# EskonzoUSB_base.net
KiCad netlist of a schematic drawn in EAGLE
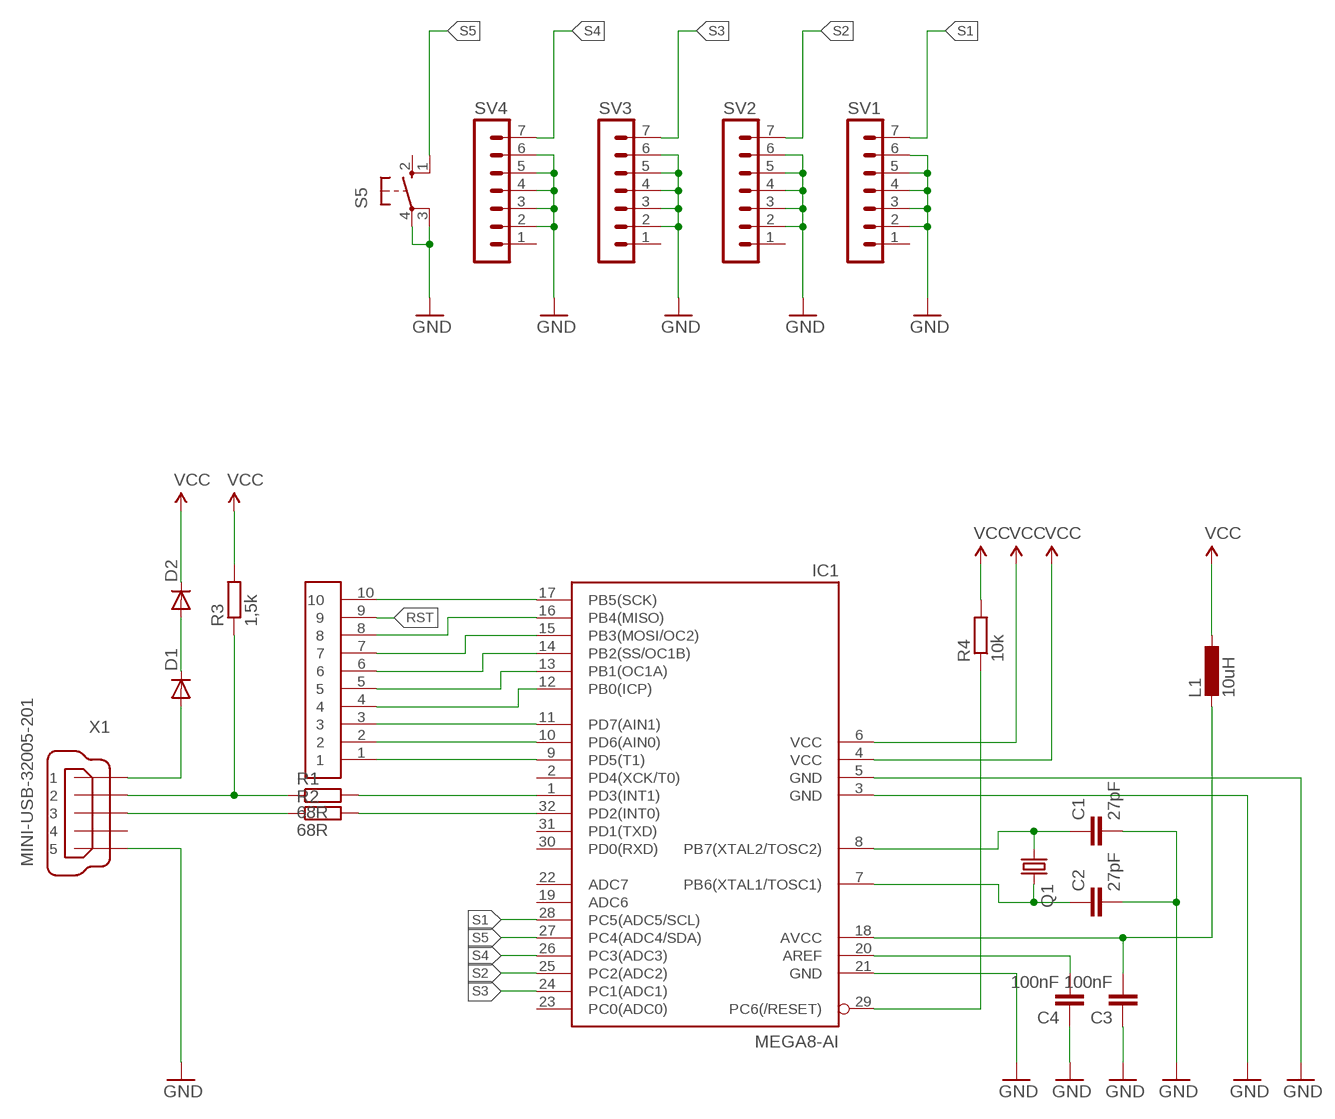
[diagram p0: schematic, sheet 1]

(export (version "E")
  (design (tool "Eeschema 10.0.6"))
  (components
    (comp (ref "C1")
      (value "27pF")
      (footprint "eagle-import:C0805")
      (libsource (lib "eagle-import") (part "C-EUC0805"))
    )
    (comp (ref "C2")
      (value "27pF")
      (footprint "eagle-import:C0805")
      (libsource (lib "eagle-import") (part "C-EUC0805"))
    )
    (comp (ref "C3")
      (value "100nF")
      (footprint "eagle-import:C0805")
      (libsource (lib "eagle-import") (part "C-EUC0805"))
    )
    (comp (ref "C4")
      (value "100nF")
      (footprint "eagle-import:C0805")
      (libsource (lib "eagle-import") (part "C-EUC0805"))
    )
    (comp (ref "D1")
      (value "DIODE-MELF-MLL41")
      (footprint "eagle-import:MELF-MLL41")
      (libsource (lib "eagle-import") (part "DIODE-MELF-MLL41"))
    )
    (comp (ref "D2")
      (value "DIODE-MELF-MLL41")
      (footprint "eagle-import:MELF-MLL41")
      (libsource (lib "eagle-import") (part "DIODE-MELF-MLL41"))
    )
    (comp (ref "IC1")
      (value "MEGA8-AI")
      (footprint "eagle-import:TQFP32-08")
      (fields (field (name "MPN") "ATMEGA8-16AU"))
      (libsource (lib "eagle-import") (part "MEGA8-AI"))
    )
    (comp (ref "L1")
      (value "10uH")
      (footprint "eagle-import:L1812")
      (libsource (lib "eagle-import") (part "L-EUL1812"))
    )
    (comp (ref "Q1")
      (value "CRYSTALHC49UP")
      (footprint "eagle-import:HC49UP")
      (libsource (lib "eagle-import") (part "CRYSTALHC49UP"))
    )
    (comp (ref "R1")
      (value "68R")
      (footprint "eagle-import:R0805")
      (libsource (lib "eagle-import") (part "R-EU_R0805"))
    )
    (comp (ref "R2")
      (value "68R")
      (footprint "eagle-import:R0805")
      (libsource (lib "eagle-import") (part "R-EU_R0805"))
    )
    (comp (ref "R3")
      (value "1,5k")
      (footprint "eagle-import:R0805")
      (libsource (lib "eagle-import") (part "R-EU_R0805"))
    )
    (comp (ref "R4")
      (value "10k")
      (footprint "eagle-import:R0805")
      (libsource (lib "eagle-import") (part "R-EU_R0805"))
    )
    (comp (ref "S5")
      (value "40-XX_SMD")
      (footprint "eagle-import:B3F-40XX_SMD")
      (libsource (lib "eagle-import") (part "40-XX_SMD"))
    )
    (comp (ref "SV1")
      (value "MA07-1_SMD")
      (footprint "eagle-import:MA07-1_SMD")
      (libsource (lib "eagle-import") (part "MA07-1_SMD"))
    )
    (comp (ref "SV2")
      (value "MA07-1_SMD")
      (footprint "eagle-import:MA07-1_SMD")
      (libsource (lib "eagle-import") (part "MA07-1_SMD"))
    )
    (comp (ref "SV3")
      (value "MA07-1_SMD")
      (footprint "eagle-import:MA07-1_SMD")
      (libsource (lib "eagle-import") (part "MA07-1_SMD"))
    )
    (comp (ref "SV4")
      (value "MA07-1_SMD")
      (footprint "eagle-import:MA07-1_SMD")
      (libsource (lib "eagle-import") (part "MA07-1_SMD"))
    )
    (comp (ref "U$1")
      (value "PINY_1X9_1.27MM_SMT")
      (footprint "eagle-import:PINY_1X9_1.27MM_SMT")
      (libsource (lib "eagle-import") (part "PINY_1X9_1.27MM_SMT"))
    )
    (comp (ref "X1")
      (value "MINI-USB-32005-201")
      (footprint "eagle-import:32005-201")
      (libsource (lib "eagle-import") (part "MINI-USB-32005-201"))
    )
  )
  (nets
    (net (code "1") (name "GND") (class "Default")
      (node (ref "C1") (pin "2") (pinfunction "2_2") (pintype "passive"))
      (node (ref "C2") (pin "2") (pinfunction "2_2") (pintype "passive"))
      (node (ref "C3") (pin "1") (pinfunction "1_1") (pintype "passive"))
      (node (ref "C4") (pin "1") (pinfunction "1_1") (pintype "passive"))
      (node (ref "IC1") (pin "21") (pinfunction "GND_21") (pintype "power_in"))
      (node (ref "IC1") (pin "3") (pinfunction "GND_3") (pintype "power_in"))
      (node (ref "IC1") (pin "5") (pinfunction "GND_5") (pintype "power_in"))
      (node (ref "S5") (pin "3") (pinfunction "P1_3") (pintype "passive"))
      (node (ref "S5") (pin "4") (pinfunction "P_4") (pintype "passive"))
      (node (ref "SV1") (pin "2") (pinfunction "2_2") (pintype "passive"))
      (node (ref "SV1") (pin "3") (pinfunction "3_3") (pintype "passive"))
      (node (ref "SV1") (pin "4") (pinfunction "4_4") (pintype "passive"))
      (node (ref "SV1") (pin "5") (pinfunction "5_5") (pintype "passive"))
      (node (ref "SV1") (pin "6") (pinfunction "6_6") (pintype "passive"))
      (node (ref "SV2") (pin "2") (pinfunction "2_2") (pintype "passive"))
      (node (ref "SV2") (pin "3") (pinfunction "3_3") (pintype "passive"))
      (node (ref "SV2") (pin "4") (pinfunction "4_4") (pintype "passive"))
      (node (ref "SV2") (pin "5") (pinfunction "5_5") (pintype "passive"))
      (node (ref "SV2") (pin "6") (pinfunction "6_6") (pintype "passive"))
      (node (ref "SV3") (pin "2") (pinfunction "2_2") (pintype "passive"))
      (node (ref "SV3") (pin "3") (pinfunction "3_3") (pintype "passive"))
      (node (ref "SV3") (pin "4") (pinfunction "4_4") (pintype "passive"))
      (node (ref "SV3") (pin "5") (pinfunction "5_5") (pintype "passive"))
      (node (ref "SV3") (pin "6") (pinfunction "6_6") (pintype "passive"))
      (node (ref "SV4") (pin "2") (pinfunction "2_2") (pintype "passive"))
      (node (ref "SV4") (pin "3") (pinfunction "3_3") (pintype "passive"))
      (node (ref "SV4") (pin "4") (pinfunction "4_4") (pintype "passive"))
      (node (ref "SV4") (pin "5") (pinfunction "5_5") (pintype "passive"))
      (node (ref "SV4") (pin "6") (pinfunction "6_6") (pintype "passive"))
      (node (ref "X1") (pin "5") (pinfunction "5_5") (pintype "passive"))
    )
    (net (code "2") (name "Net-(D1-PadA)") (class "Default")
      (node (ref "D1") (pin "A") (pinfunction "A_A") (pintype "passive"))
      (node (ref "X1") (pin "1") (pinfunction "1_1") (pintype "passive"))
    )
    (net (code "3") (name "Net-(D1-PadC)") (class "Default")
      (node (ref "D1") (pin "C") (pinfunction "C_C") (pintype "passive"))
      (node (ref "D2") (pin "A") (pinfunction "A_A") (pintype "passive"))
    )
    (net (code "4") (name "Net-(IC1-AREF)") (class "Default")
      (node (ref "C4") (pin "2") (pinfunction "2_2") (pintype "passive"))
      (node (ref "IC1") (pin "20") (pinfunction "AREF_20") (pintype "passive"))
    )
    (net (code "5") (name "Net-(IC1-AVCC)") (class "Default")
      (node (ref "C3") (pin "2") (pinfunction "2_2") (pintype "passive"))
      (node (ref "IC1") (pin "18") (pinfunction "AVCC_18") (pintype "power_in"))
      (node (ref "L1") (pin "2") (pinfunction "2_2") (pintype "passive"))
    )
    (net (code "6") (name "Net-(IC1-PB0(ICP))") (class "Default")
      (node (ref "IC1") (pin "12") (pinfunction "PB0(ICP)_12") (pintype "bidirectional"))
      (node (ref "U$1") (pin "4") (pinfunction "4_4") (pintype "passive"))
    )
    (net (code "7") (name "Net-(IC1-PB1(OC1A))") (class "Default")
      (node (ref "IC1") (pin "13") (pinfunction "PB1(OC1A)_13") (pintype "bidirectional"))
      (node (ref "U$1") (pin "5") (pinfunction "5_5") (pintype "passive"))
    )
    (net (code "8") (name "Net-(IC1-PB2(SS{slash}OC1B))") (class "Default")
      (node (ref "IC1") (pin "14") (pinfunction "PB2(SS/OC1B)_14") (pintype "bidirectional"))
      (node (ref "U$1") (pin "6") (pinfunction "6_6") (pintype "passive"))
    )
    (net (code "9") (name "Net-(IC1-PB3(MOSI{slash}OC2))") (class "Default")
      (node (ref "IC1") (pin "15") (pinfunction "PB3(MOSI/OC2)_15") (pintype "bidirectional"))
      (node (ref "U$1") (pin "7") (pinfunction "7_7") (pintype "passive"))
    )
    (net (code "10") (name "Net-(IC1-PB4(MISO))") (class "Default")
      (node (ref "IC1") (pin "16") (pinfunction "PB4(MISO)_16") (pintype "bidirectional"))
      (node (ref "U$1") (pin "8") (pinfunction "8_8") (pintype "passive"))
    )
    (net (code "11") (name "Net-(IC1-PB5(SCK))") (class "Default")
      (node (ref "IC1") (pin "17") (pinfunction "PB5(SCK)_17") (pintype "bidirectional"))
      (node (ref "U$1") (pin "10") (pinfunction "10_10") (pintype "passive"))
    )
    (net (code "12") (name "Net-(IC1-PB6(XTAL1{slash}TOSC1))") (class "Default")
      (node (ref "C2") (pin "1") (pinfunction "1_1") (pintype "passive"))
      (node (ref "IC1") (pin "7") (pinfunction "PB6(XTAL1/TOSC1)_7") (pintype "bidirectional"))
      (node (ref "Q1") (pin "2") (pinfunction "2_2") (pintype "passive"))
    )
    (net (code "13") (name "Net-(IC1-PB7(XTAL2{slash}TOSC2))") (class "Default")
      (node (ref "C1") (pin "1") (pinfunction "1_1") (pintype "passive"))
      (node (ref "IC1") (pin "8") (pinfunction "PB7(XTAL2/TOSC2)_8") (pintype "bidirectional"))
      (node (ref "Q1") (pin "1") (pinfunction "1_1") (pintype "passive"))
    )
    (net (code "14") (name "Net-(IC1-PD2(INT0))") (class "Default")
      (node (ref "IC1") (pin "32") (pinfunction "PD2(INT0)_32") (pintype "bidirectional"))
      (node (ref "R2") (pin "2") (pinfunction "2_2") (pintype "passive"))
    )
    (net (code "15") (name "Net-(IC1-PD3(INT1))") (class "Default")
      (node (ref "IC1") (pin "1") (pinfunction "PD3(INT1)_1") (pintype "bidirectional"))
      (node (ref "R1") (pin "2") (pinfunction "2_2") (pintype "passive"))
    )
    (net (code "16") (name "Net-(IC1-PD5(T1))") (class "Default")
      (node (ref "IC1") (pin "9") (pinfunction "PD5(T1)_9") (pintype "bidirectional"))
      (node (ref "U$1") (pin "1") (pinfunction "1_1") (pintype "passive"))
    )
    (net (code "17") (name "Net-(IC1-PD6(AIN0))") (class "Default")
      (node (ref "IC1") (pin "10") (pinfunction "PD6(AIN0)_10") (pintype "bidirectional"))
      (node (ref "U$1") (pin "2") (pinfunction "2_2") (pintype "passive"))
    )
    (net (code "18") (name "Net-(IC1-PD7(AIN1))") (class "Default")
      (node (ref "IC1") (pin "11") (pinfunction "PD7(AIN1)_11") (pintype "bidirectional"))
      (node (ref "U$1") (pin "3") (pinfunction "3_3") (pintype "passive"))
    )
    (net (code "19") (name "Net-(R1-Pad1)") (class "Default")
      (node (ref "R1") (pin "1") (pinfunction "1_1") (pintype "passive"))
      (node (ref "R3") (pin "1") (pinfunction "1_1") (pintype "passive"))
      (node (ref "X1") (pin "2") (pinfunction "2_2") (pintype "passive"))
    )
    (net (code "20") (name "Net-(R2-Pad1)") (class "Default")
      (node (ref "R2") (pin "1") (pinfunction "1_1") (pintype "passive"))
      (node (ref "X1") (pin "3") (pinfunction "3_3") (pintype "passive"))
    )
    (net (code "21") (name "RST") (class "Default")
      (node (ref "IC1") (pin "29") (pinfunction "PC6(/RESET)_29") (pintype "bidirectional"))
      (node (ref "R4") (pin "1") (pinfunction "1_1") (pintype "passive"))
      (node (ref "U$1") (pin "9") (pinfunction "9_9") (pintype "passive"))
    )
    (net (code "22") (name "S1") (class "Default")
      (node (ref "IC1") (pin "28") (pinfunction "PC5(ADC5/SCL)_28") (pintype "bidirectional"))
      (node (ref "SV1") (pin "7") (pinfunction "7_7") (pintype "passive"))
    )
    (net (code "23") (name "S2") (class "Default")
      (node (ref "IC1") (pin "25") (pinfunction "PC2(ADC2)_25") (pintype "bidirectional"))
      (node (ref "SV2") (pin "7") (pinfunction "7_7") (pintype "passive"))
    )
    (net (code "24") (name "S3") (class "Default")
      (node (ref "IC1") (pin "24") (pinfunction "PC1(ADC1)_24") (pintype "bidirectional"))
      (node (ref "SV3") (pin "7") (pinfunction "7_7") (pintype "passive"))
    )
    (net (code "25") (name "S4") (class "Default")
      (node (ref "IC1") (pin "26") (pinfunction "PC3(ADC3)_26") (pintype "bidirectional"))
      (node (ref "SV4") (pin "7") (pinfunction "7_7") (pintype "passive"))
    )
    (net (code "26") (name "S5") (class "Default")
      (node (ref "IC1") (pin "27") (pinfunction "PC4(ADC4/SDA)_27") (pintype "bidirectional"))
      (node (ref "S5") (pin "1") (pinfunction "S1_1") (pintype "passive"))
    )
    (net (code "27") (name "VCC") (class "Default")
      (node (ref "D2") (pin "C") (pinfunction "C_C") (pintype "passive"))
      (node (ref "IC1") (pin "4") (pinfunction "VCC_4") (pintype "power_in"))
      (node (ref "IC1") (pin "6") (pinfunction "VCC_6") (pintype "power_in"))
      (node (ref "L1") (pin "1") (pinfunction "1_1") (pintype "passive"))
      (node (ref "R3") (pin "2") (pinfunction "2_2") (pintype "passive"))
      (node (ref "R4") (pin "2") (pinfunction "2_2") (pintype "passive"))
    )
    (net (code "28") (name "unconnected-(IC1-ADC6-Pad19)") (class "Default")
      (node (ref "IC1") (pin "19") (pinfunction "ADC6_19") (pintype "bidirectional"))
    )
    (net (code "29") (name "unconnected-(IC1-ADC7-Pad22)") (class "Default")
      (node (ref "IC1") (pin "22") (pinfunction "ADC7_22") (pintype "bidirectional"))
    )
    (net (code "30") (name "unconnected-(IC1-PC0(ADC0)-Pad23)") (class "Default")
      (node (ref "IC1") (pin "23") (pinfunction "PC0(ADC0)_23") (pintype "bidirectional"))
    )
    (net (code "31") (name "unconnected-(IC1-PD0(RXD)-Pad30)") (class "Default")
      (node (ref "IC1") (pin "30") (pinfunction "PD0(RXD)_30") (pintype "bidirectional"))
    )
    (net (code "32") (name "unconnected-(IC1-PD1(TXD)-Pad31)") (class "Default")
      (node (ref "IC1") (pin "31") (pinfunction "PD1(TXD)_31") (pintype "bidirectional"))
    )
    (net (code "33") (name "unconnected-(IC1-PD4(XCK{slash}T0)-Pad2)") (class "Default")
      (node (ref "IC1") (pin "2") (pinfunction "PD4(XCK/T0)_2") (pintype "bidirectional"))
    )
    (net (code "34") (name "unconnected-(S5-S-Pad2)") (class "Default")
      (node (ref "S5") (pin "2") (pinfunction "S_2") (pintype "passive"))
    )
    (net (code "35") (name "unconnected-(SV1-Pad1)") (class "Default")
      (node (ref "SV1") (pin "1") (pinfunction "1_1") (pintype "passive"))
    )
    (net (code "36") (name "unconnected-(SV2-Pad1)") (class "Default")
      (node (ref "SV2") (pin "1") (pinfunction "1_1") (pintype "passive"))
    )
    (net (code "37") (name "unconnected-(SV3-Pad1)") (class "Default")
      (node (ref "SV3") (pin "1") (pinfunction "1_1") (pintype "passive"))
    )
    (net (code "38") (name "unconnected-(SV4-Pad1)") (class "Default")
      (node (ref "SV4") (pin "1") (pinfunction "1_1") (pintype "passive"))
    )
    (net (code "39") (name "unconnected-(X1-Pad4)") (class "Default")
      (node (ref "X1") (pin "4") (pinfunction "4_4") (pintype "passive"))
    )
  )
)
